# ARE_adaptadora_PIC_18-20pin.net
KiCad netlist of a schematic drawn in EAGLE
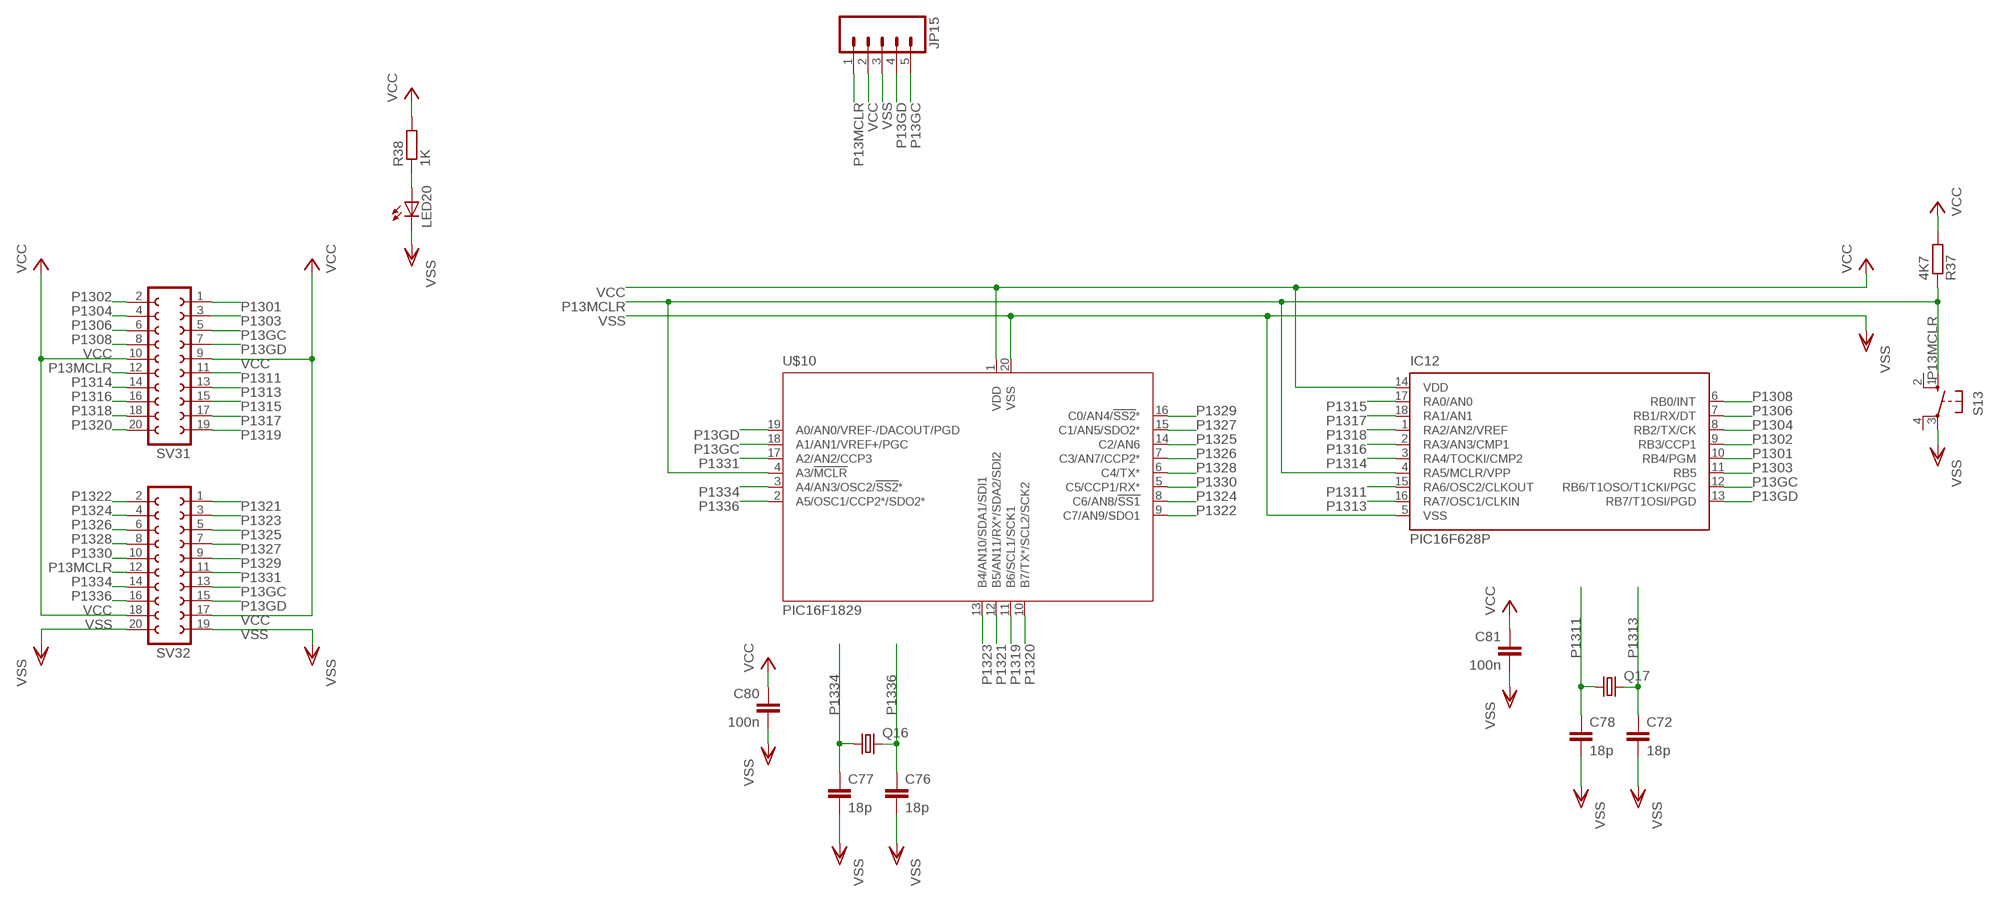
[diagram p0: schematic, sheet 1]

(export (version "E")
  (design (tool "Eeschema 10.0.6"))
  (components
    (comp (ref "C72")
      (value "18p")
      (footprint "eagle-import:C0805")
      (libsource (lib "eagle-import") (part "C-EUC0805"))
    )
    (comp (ref "C76")
      (value "18p")
      (footprint "eagle-import:C0805")
      (libsource (lib "eagle-import") (part "C-EUC0805"))
    )
    (comp (ref "C77")
      (value "18p")
      (footprint "eagle-import:C0805")
      (libsource (lib "eagle-import") (part "C-EUC0805"))
    )
    (comp (ref "C78")
      (value "18p")
      (footprint "eagle-import:C0805")
      (libsource (lib "eagle-import") (part "C-EUC0805"))
    )
    (comp (ref "C80")
      (value "100n")
      (footprint "eagle-import:C0805")
      (libsource (lib "eagle-import") (part "C-EUC0805"))
    )
    (comp (ref "C81")
      (value "100n")
      (footprint "eagle-import:C0805")
      (libsource (lib "eagle-import") (part "C-EUC0805"))
    )
    (comp (ref "IC12")
      (value "PIC16F628P")
      (footprint "eagle-import:DIL18")
      (fields (field (name "MF") "MICROCHIP") (field (name "MPN") "PIC16F628-04I/P"))
      (libsource (lib "eagle-import") (part "PIC16F62P8"))
    )
    (comp (ref "JP15")
      (value "M05PTH")
      (footprint "eagle-import:1X05")
      (libsource (lib "eagle-import") (part "M05PTH"))
    )
    (comp (ref "LED20")
      (value "LEDCHIPLED_0805")
      (footprint "eagle-import:CHIPLED_0805")
      (libsource (lib "eagle-import") (part "LEDCHIPLED_0805"))
    )
    (comp (ref "Q16")
      (value "CRYSTALHC18U-V")
      (footprint "eagle-import:HC18U-V")
      (libsource (lib "eagle-import") (part "CRYSTALHC18U-V"))
    )
    (comp (ref "Q17")
      (value "CRYSTALHC18U-V")
      (footprint "eagle-import:HC18U-V")
      (libsource (lib "eagle-import") (part "CRYSTALHC18U-V"))
    )
    (comp (ref "R37")
      (value "4K7")
      (footprint "eagle-import:R0805")
      (libsource (lib "eagle-import") (part "R-EU_R0805"))
    )
    (comp (ref "R38")
      (value "1K")
      (footprint "eagle-import:R0805")
      (libsource (lib "eagle-import") (part "R-EU_R0805"))
    )
    (comp (ref "S13")
      (value "10-XX")
      (footprint "eagle-import:B3F-10XX")
      (fields
        (field (name "MPN") "B3F-1000")
        (field (name "MPN_1") "B3F-1000")
        (field (name "OC_FARNELL") "176432")
        (field (name "OC_NEWARK") "36M3542")
      )
      (libsource (lib "eagle-import") (part "10-XX"))
    )
    (comp (ref "SV31")
      (value "FE10-2W")
      (footprint "eagle-import:FE10-2W")
      (libsource (lib "eagle-import") (part "FE10-2W"))
    )
    (comp (ref "SV32")
      (value "FE10-2W")
      (footprint "eagle-import:FE10-2W")
      (libsource (lib "eagle-import") (part "FE10-2W"))
    )
    (comp (ref "U$10")
      (value "PIC16F1829")
      (footprint "eagle-import:DIL20")
      (libsource (lib "eagle-import") (part "PIC16F1829"))
    )
  )
  (nets
    (net (code "1") (name "/P13GC") (class "Default")
      (node (ref "IC12") (pin "12") (pinfunction "RB6/T1OSO/T1CKI/PGC_12") (pintype "bidirectional"))
      (node (ref "JP15") (pin "5") (pinfunction "5_5") (pintype "passive"))
      (node (ref "SV31") (pin "5") (pinfunction "5_5") (pintype "passive"))
      (node (ref "SV32") (pin "13") (pinfunction "13_13") (pintype "passive"))
      (node (ref "U$10") (pin "18") (pinfunction "A1/AN1/VREF+/PGC_18") (pintype "bidirectional"))
    )
    (net (code "2") (name "/P13GD") (class "Default")
      (node (ref "IC12") (pin "13") (pinfunction "RB7/T1OSI/PGD_13") (pintype "bidirectional"))
      (node (ref "JP15") (pin "4") (pinfunction "4_4") (pintype "passive"))
      (node (ref "SV31") (pin "7") (pinfunction "7_7") (pintype "passive"))
      (node (ref "SV32") (pin "15") (pinfunction "15_15") (pintype "passive"))
      (node (ref "U$10") (pin "19") (pinfunction "A0/AN0/VREF-/DACOUT/PGD_19") (pintype "bidirectional"))
    )
    (net (code "3") (name "/P13MCLR") (class "Default")
      (node (ref "IC12") (pin "4") (pinfunction "RA5/MCLR/VPP_4") (pintype "bidirectional"))
      (node (ref "JP15") (pin "1") (pinfunction "1_1") (pintype "passive"))
      (node (ref "R37") (pin "1") (pinfunction "1_1") (pintype "passive"))
      (node (ref "S13") (pin "1") (pinfunction "S_1") (pintype "passive"))
      (node (ref "SV31") (pin "12") (pinfunction "12_12") (pintype "passive"))
      (node (ref "SV32") (pin "12") (pinfunction "12_12") (pintype "passive"))
      (node (ref "U$10") (pin "4") (pinfunction "A3/~{MCLR}_4") (pintype "bidirectional"))
    )
    (net (code "4") (name "/P1301") (class "Default")
      (node (ref "IC12") (pin "10") (pinfunction "RB4/PGM_10") (pintype "bidirectional"))
      (node (ref "SV31") (pin "1") (pinfunction "1_1") (pintype "passive"))
    )
    (net (code "5") (name "/P1302") (class "Default")
      (node (ref "IC12") (pin "9") (pinfunction "RB3/CCP1_9") (pintype "bidirectional"))
      (node (ref "SV31") (pin "2") (pinfunction "2_2") (pintype "passive"))
    )
    (net (code "6") (name "/P1303") (class "Default")
      (node (ref "IC12") (pin "11") (pinfunction "RB5_11") (pintype "bidirectional"))
      (node (ref "SV31") (pin "3") (pinfunction "3_3") (pintype "passive"))
    )
    (net (code "7") (name "/P1304") (class "Default")
      (node (ref "IC12") (pin "8") (pinfunction "RB2/TX/CK_8") (pintype "bidirectional"))
      (node (ref "SV31") (pin "4") (pinfunction "4_4") (pintype "passive"))
    )
    (net (code "8") (name "/P1306") (class "Default")
      (node (ref "IC12") (pin "7") (pinfunction "RB1/RX/DT_7") (pintype "bidirectional"))
      (node (ref "SV31") (pin "6") (pinfunction "6_6") (pintype "passive"))
    )
    (net (code "9") (name "/P1308") (class "Default")
      (node (ref "IC12") (pin "6") (pinfunction "RB0/INT_6") (pintype "bidirectional"))
      (node (ref "SV31") (pin "8") (pinfunction "8_8") (pintype "passive"))
    )
    (net (code "10") (name "/P1311") (class "Default")
      (node (ref "C78") (pin "1") (pinfunction "1_1") (pintype "passive"))
      (node (ref "IC12") (pin "15") (pinfunction "RA6/OSC2/CLKOUT_15") (pintype "bidirectional"))
      (node (ref "Q17") (pin "1") (pinfunction "1_1") (pintype "passive"))
      (node (ref "SV31") (pin "11") (pinfunction "11_11") (pintype "passive"))
    )
    (net (code "11") (name "/P1313") (class "Default")
      (node (ref "C72") (pin "1") (pinfunction "1_1") (pintype "passive"))
      (node (ref "IC12") (pin "16") (pinfunction "RA7/OSC1/CLKIN_16") (pintype "bidirectional"))
      (node (ref "Q17") (pin "2") (pinfunction "2_2") (pintype "passive"))
      (node (ref "SV31") (pin "13") (pinfunction "13_13") (pintype "passive"))
    )
    (net (code "12") (name "/P1314") (class "Default")
      (node (ref "IC12") (pin "3") (pinfunction "RA4/TOCKI/CMP2_3") (pintype "bidirectional"))
      (node (ref "SV31") (pin "14") (pinfunction "14_14") (pintype "passive"))
    )
    (net (code "13") (name "/P1315") (class "Default")
      (node (ref "IC12") (pin "17") (pinfunction "RA0/AN0_17") (pintype "bidirectional"))
      (node (ref "SV31") (pin "15") (pinfunction "15_15") (pintype "passive"))
    )
    (net (code "14") (name "/P1316") (class "Default")
      (node (ref "IC12") (pin "2") (pinfunction "RA3/AN3/CMP1_2") (pintype "bidirectional"))
      (node (ref "SV31") (pin "16") (pinfunction "16_16") (pintype "passive"))
    )
    (net (code "15") (name "/P1317") (class "Default")
      (node (ref "IC12") (pin "18") (pinfunction "RA1/AN1_18") (pintype "bidirectional"))
      (node (ref "SV31") (pin "17") (pinfunction "17_17") (pintype "passive"))
    )
    (net (code "16") (name "/P1318") (class "Default")
      (node (ref "IC12") (pin "1") (pinfunction "RA2/AN2/VREF_1") (pintype "bidirectional"))
      (node (ref "SV31") (pin "18") (pinfunction "18_18") (pintype "passive"))
    )
    (net (code "17") (name "/P1319") (class "Default")
      (node (ref "SV31") (pin "19") (pinfunction "19_19") (pintype "passive"))
      (node (ref "U$10") (pin "11") (pinfunction "B6/SCL1/SCK1_11") (pintype "bidirectional"))
    )
    (net (code "18") (name "/P1320") (class "Default")
      (node (ref "SV31") (pin "20") (pinfunction "20_20") (pintype "passive"))
      (node (ref "U$10") (pin "10") (pinfunction "B7/TX*/SCL2/SCK2_10") (pintype "bidirectional"))
    )
    (net (code "19") (name "/P1321") (class "Default")
      (node (ref "SV32") (pin "1") (pinfunction "1_1") (pintype "passive"))
      (node (ref "U$10") (pin "12") (pinfunction "B5/AN11/RX*/SDA2/SDI2_12") (pintype "bidirectional"))
    )
    (net (code "20") (name "/P1322") (class "Default")
      (node (ref "SV32") (pin "2") (pinfunction "2_2") (pintype "passive"))
      (node (ref "U$10") (pin "9") (pinfunction "C7/AN9/SDO1_9") (pintype "bidirectional"))
    )
    (net (code "21") (name "/P1323") (class "Default")
      (node (ref "SV32") (pin "3") (pinfunction "3_3") (pintype "passive"))
      (node (ref "U$10") (pin "13") (pinfunction "B4/AN10/SDA1/SDI1_13") (pintype "input"))
    )
    (net (code "22") (name "/P1324") (class "Default")
      (node (ref "SV32") (pin "4") (pinfunction "4_4") (pintype "passive"))
      (node (ref "U$10") (pin "8") (pinfunction "C6/AN8/~{SS1}_8") (pintype "bidirectional"))
    )
    (net (code "23") (name "/P1325") (class "Default")
      (node (ref "SV32") (pin "5") (pinfunction "5_5") (pintype "passive"))
      (node (ref "U$10") (pin "14") (pinfunction "C2/AN6_14") (pintype "bidirectional"))
    )
    (net (code "24") (name "/P1326") (class "Default")
      (node (ref "SV32") (pin "6") (pinfunction "6_6") (pintype "passive"))
      (node (ref "U$10") (pin "7") (pinfunction "C3/AN7/CCP2*_7") (pintype "bidirectional"))
    )
    (net (code "25") (name "/P1327") (class "Default")
      (node (ref "SV32") (pin "7") (pinfunction "7_7") (pintype "passive"))
      (node (ref "U$10") (pin "15") (pinfunction "C1/AN5/SDO2*_15") (pintype "bidirectional"))
    )
    (net (code "26") (name "/P1328") (class "Default")
      (node (ref "SV32") (pin "8") (pinfunction "8_8") (pintype "passive"))
      (node (ref "U$10") (pin "6") (pinfunction "C4/TX*_6") (pintype "bidirectional"))
    )
    (net (code "27") (name "/P1329") (class "Default")
      (node (ref "SV32") (pin "9") (pinfunction "9_9") (pintype "passive"))
      (node (ref "U$10") (pin "16") (pinfunction "C0/AN4/~{SS2}*_16") (pintype "bidirectional"))
    )
    (net (code "28") (name "/P1330") (class "Default")
      (node (ref "SV32") (pin "10") (pinfunction "10_10") (pintype "passive"))
      (node (ref "U$10") (pin "5") (pinfunction "C5/CCP1/RX*_5") (pintype "bidirectional"))
    )
    (net (code "29") (name "/P1331") (class "Default")
      (node (ref "SV32") (pin "11") (pinfunction "11_11") (pintype "passive"))
      (node (ref "U$10") (pin "17") (pinfunction "A2/AN2/CCP3_17") (pintype "bidirectional"))
    )
    (net (code "30") (name "/P1334") (class "Default")
      (node (ref "C77") (pin "1") (pinfunction "1_1") (pintype "passive"))
      (node (ref "Q16") (pin "1") (pinfunction "1_1") (pintype "passive"))
      (node (ref "SV32") (pin "14") (pinfunction "14_14") (pintype "passive"))
      (node (ref "U$10") (pin "3") (pinfunction "A4/AN3/OSC2/~{SS2}*_3") (pintype "bidirectional"))
    )
    (net (code "31") (name "/P1336") (class "Default")
      (node (ref "C76") (pin "1") (pinfunction "1_1") (pintype "passive"))
      (node (ref "Q16") (pin "2") (pinfunction "2_2") (pintype "passive"))
      (node (ref "SV32") (pin "16") (pinfunction "16_16") (pintype "passive"))
      (node (ref "U$10") (pin "2") (pinfunction "A5/OSC1/CCP2*/SDO2*_2") (pintype "bidirectional"))
    )
    (net (code "32") (name "Net-(LED20-PadA)") (class "Default")
      (node (ref "LED20") (pin "A") (pinfunction "A_A") (pintype "passive"))
      (node (ref "R38") (pin "1") (pinfunction "1_1") (pintype "passive"))
    )
    (net (code "33") (name "VCC") (class "Default")
      (node (ref "C80") (pin "1") (pinfunction "1_1") (pintype "passive"))
      (node (ref "C81") (pin "1") (pinfunction "1_1") (pintype "passive"))
      (node (ref "IC12") (pin "14") (pinfunction "VDD_14") (pintype "power_in"))
      (node (ref "JP15") (pin "2") (pinfunction "2_2") (pintype "passive"))
      (node (ref "R37") (pin "2") (pinfunction "2_2") (pintype "passive"))
      (node (ref "R38") (pin "2") (pinfunction "2_2") (pintype "passive"))
      (node (ref "SV31") (pin "10") (pinfunction "10_10") (pintype "passive"))
      (node (ref "SV31") (pin "9") (pinfunction "9_9") (pintype "passive"))
      (node (ref "SV32") (pin "17") (pinfunction "17_17") (pintype "passive"))
      (node (ref "SV32") (pin "18") (pinfunction "18_18") (pintype "passive"))
      (node (ref "U$10") (pin "1") (pinfunction "VDD_1") (pintype "power_in"))
    )
    (net (code "34") (name "VSS") (class "Default")
      (node (ref "C72") (pin "2") (pinfunction "2_2") (pintype "passive"))
      (node (ref "C76") (pin "2") (pinfunction "2_2") (pintype "passive"))
      (node (ref "C77") (pin "2") (pinfunction "2_2") (pintype "passive"))
      (node (ref "C78") (pin "2") (pinfunction "2_2") (pintype "passive"))
      (node (ref "C80") (pin "2") (pinfunction "2_2") (pintype "passive"))
      (node (ref "C81") (pin "2") (pinfunction "2_2") (pintype "passive"))
      (node (ref "IC12") (pin "5") (pinfunction "VSS_5") (pintype "power_in"))
      (node (ref "JP15") (pin "3") (pinfunction "3_3") (pintype "passive"))
      (node (ref "LED20") (pin "C") (pinfunction "C_C") (pintype "passive"))
      (node (ref "S13") (pin "3") (pinfunction "P_3") (pintype "passive"))
      (node (ref "SV32") (pin "19") (pinfunction "19_19") (pintype "passive"))
      (node (ref "SV32") (pin "20") (pinfunction "20_20") (pintype "passive"))
      (node (ref "U$10") (pin "20") (pinfunction "VSS_20") (pintype "power_in"))
    )
    (net (code "35") (name "unconnected-(S13-P1-Pad4)") (class "Default")
      (node (ref "S13") (pin "4") (pinfunction "P1_4") (pintype "passive"))
    )
    (net (code "36") (name "unconnected-(S13-S1-Pad2)") (class "Default")
      (node (ref "S13") (pin "2") (pinfunction "S1_2") (pintype "passive"))
    )
  )
)
